# QCopterMV_DCMI_Sch.net
KiCad netlist of a schematic drawn in Altium Designer
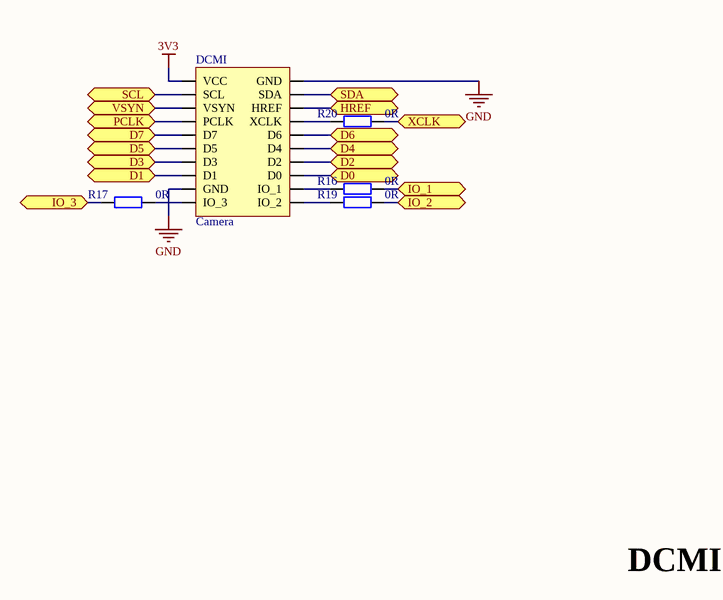
[diagram p0: QCopterMV_DCMI_Sch.SchDoc]

(export (version "E")
  (design (tool "Eeschema 10.0.6"))
  (components
    (comp (ref "DCMI")
      (value "Camera")
      (footprint "PCB_Module:CAMERA")
      (description "Module")
      (libsource (lib "SCH_Module") (part "Camera"))
    )
    (comp (ref "R16")
      (value "0R")
      (footprint "PCB_Passive:RES_0603")
      (description "Resistor")
      (fields (field (name "Comment") "Res_0603"))
      (libsource (lib "SCH_Passive") (part "Res_0603"))
    )
    (comp (ref "R17")
      (value "0R")
      (footprint "PCB_Passive:RES_0603")
      (description "Resistor")
      (fields (field (name "Comment") "Res_0603"))
      (libsource (lib "SCH_Passive") (part "Res_0603"))
    )
    (comp (ref "R19")
      (value "0R")
      (footprint "PCB_Passive:RES_0603")
      (description "Resistor")
      (fields (field (name "Comment") "Res_0603"))
      (libsource (lib "SCH_Passive") (part "Res_0603"))
    )
    (comp (ref "R20")
      (value "0R")
      (footprint "PCB_Passive:RES_0603")
      (description "Resistor")
      (fields (field (name "Comment") "Res_0603"))
      (libsource (lib "SCH_Passive") (part "Res_0603"))
    )
  )
  (nets
    (net (code "1") (name "/D0") (class "Default")
      (node (ref "DCMI") (pin "16") (pinfunction "D0_16") (pintype "passive"))
    )
    (net (code "2") (name "/D1") (class "Default")
      (node (ref "DCMI") (pin "15") (pinfunction "D1_15") (pintype "passive"))
    )
    (net (code "3") (name "/D2") (class "Default")
      (node (ref "DCMI") (pin "14") (pinfunction "D2_14") (pintype "passive"))
    )
    (net (code "4") (name "/D3") (class "Default")
      (node (ref "DCMI") (pin "13") (pinfunction "D3_13") (pintype "passive"))
    )
    (net (code "5") (name "/D4") (class "Default")
      (node (ref "DCMI") (pin "12") (pinfunction "D4_12") (pintype "passive"))
    )
    (net (code "6") (name "/D5") (class "Default")
      (node (ref "DCMI") (pin "11") (pinfunction "D5_11") (pintype "passive"))
    )
    (net (code "7") (name "/D6") (class "Default")
      (node (ref "DCMI") (pin "10") (pinfunction "D6_10") (pintype "passive"))
    )
    (net (code "8") (name "/D7") (class "Default")
      (node (ref "DCMI") (pin "9") (pinfunction "D7_9") (pintype "passive"))
    )
    (net (code "9") (name "/HREF") (class "Default")
      (node (ref "DCMI") (pin "6") (pinfunction "HREF_6") (pintype "passive"))
    )
    (net (code "10") (name "/IO_1") (class "Default")
      (node (ref "R16") (pin "2") (pinfunction "2_2") (pintype "passive"))
    )
    (net (code "11") (name "/IO_2") (class "Default")
      (node (ref "R19") (pin "2") (pinfunction "2_2") (pintype "passive"))
    )
    (net (code "12") (name "/IO_3") (class "Default")
      (node (ref "R17") (pin "1") (pinfunction "1_1") (pintype "passive"))
    )
    (net (code "13") (name "/PCLK") (class "Default")
      (node (ref "DCMI") (pin "7") (pinfunction "PCLK_7") (pintype "passive"))
    )
    (net (code "14") (name "/SCL") (class "Default")
      (node (ref "DCMI") (pin "3") (pinfunction "SCL_3") (pintype "passive"))
    )
    (net (code "15") (name "/SDA") (class "Default")
      (node (ref "DCMI") (pin "4") (pinfunction "SDA_4") (pintype "passive"))
    )
    (net (code "16") (name "/VSYN") (class "Default")
      (node (ref "DCMI") (pin "5") (pinfunction "VSYN_5") (pintype "passive"))
    )
    (net (code "17") (name "/XCLK") (class "Default")
      (node (ref "R20") (pin "2") (pinfunction "2_2") (pintype "passive"))
    )
    (net (code "18") (name "3V3") (class "Default")
      (node (ref "DCMI") (pin "1") (pinfunction "VCC_1") (pintype "passive"))
    )
    (net (code "19") (name "GND") (class "Default")
      (node (ref "DCMI") (pin "17") (pinfunction "GND_17") (pintype "passive"))
      (node (ref "DCMI") (pin "2") (pinfunction "GND_2") (pintype "passive"))
    )
    (net (code "20") (name "Net-(DCMI-IO_1)") (class "Default")
      (node (ref "DCMI") (pin "18") (pinfunction "IO_1_18") (pintype "passive"))
      (node (ref "R16") (pin "1") (pinfunction "1_1") (pintype "passive"))
    )
    (net (code "21") (name "Net-(DCMI-IO_2)") (class "Default")
      (node (ref "DCMI") (pin "20") (pinfunction "IO_2_20") (pintype "passive"))
      (node (ref "R19") (pin "1") (pinfunction "1_1") (pintype "passive"))
    )
    (net (code "22") (name "Net-(DCMI-IO_3)") (class "Default")
      (node (ref "DCMI") (pin "19") (pinfunction "IO_3_19") (pintype "passive"))
      (node (ref "R17") (pin "2") (pinfunction "2_2") (pintype "passive"))
    )
    (net (code "23") (name "Net-(DCMI-XCLK)") (class "Default")
      (node (ref "DCMI") (pin "8") (pinfunction "XCLK_8") (pintype "passive"))
      (node (ref "R20") (pin "1") (pinfunction "1_1") (pintype "passive"))
    )
  )
)
